# HexSwitch.net
KiCad netlist of a schematic drawn in Altium Designer
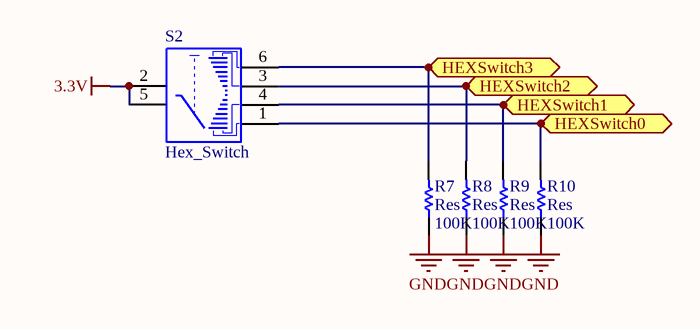
[diagram p0: HexSwitch.SchDoc]

(export (version "E")
  (design (tool "Eeschema 10.0.6"))
  (components
    (comp (ref "R7")
      (value "Res")
      (footprint "2012[0805]")
      (description "Semiconductor Resistor")
      (fields (field (name "ALTIUM_VALUE") "100K") (field (name "PUBLISHER") "Altium Limited"))
      (libsource (lib "KN2CLib") (part "Res"))
    )
    (comp (ref "R8")
      (value "Res")
      (footprint "2012[0805]")
      (description "Semiconductor Resistor")
      (fields (field (name "ALTIUM_VALUE") "100K") (field (name "PUBLISHER") "Altium Limited"))
      (libsource (lib "KN2CLib") (part "Res"))
    )
    (comp (ref "R9")
      (value "Res")
      (footprint "2012[0805]")
      (description "Semiconductor Resistor")
      (fields (field (name "ALTIUM_VALUE") "100K") (field (name "PUBLISHER") "Altium Limited"))
      (libsource (lib "KN2CLib") (part "Res"))
    )
    (comp (ref "R10")
      (value "Res")
      (footprint "2012[0805]")
      (description "Semiconductor Resistor")
      (fields (field (name "ALTIUM_VALUE") "100K") (field (name "PUBLISHER") "Altium Limited"))
      (libsource (lib "KN2CLib") (part "Res"))
    )
    (comp (ref "S2")
      (value "Hex_Switch")
      (footprint "SW-HEX")
      (description "SW-Hex")
      (fields (field (name "PUBLISHER") "Altium Limited"))
      (libsource (lib "KN2CLib") (part "SW-Hex"))
    )
  )
  (nets
    (net (code "1") (name "/HEXSwitch0") (class "Default")
      (node (ref "R10") (pin "2") (pinfunction "2_2") (pintype "passive"))
      (node (ref "S2") (pin "1") (pinfunction "1_1") (pintype "passive"))
    )
    (net (code "2") (name "/HEXSwitch1") (class "Default")
      (node (ref "R9") (pin "2") (pinfunction "2_2") (pintype "passive"))
      (node (ref "S2") (pin "4") (pinfunction "4_4") (pintype "passive"))
    )
    (net (code "3") (name "/HEXSwitch2") (class "Default")
      (node (ref "R8") (pin "2") (pinfunction "2_2") (pintype "passive"))
      (node (ref "S2") (pin "3") (pinfunction "3_3") (pintype "passive"))
    )
    (net (code "4") (name "/HEXSwitch3") (class "Default")
      (node (ref "R7") (pin "2") (pinfunction "2_2") (pintype "passive"))
      (node (ref "S2") (pin "6") (pinfunction "6_6") (pintype "passive"))
    )
    (net (code "5") (name "3.3V") (class "Default")
      (node (ref "S2") (pin "2") (pinfunction "2_2") (pintype "passive"))
      (node (ref "S2") (pin "5") (pinfunction "5_5") (pintype "passive"))
    )
    (net (code "6") (name "GND") (class "Default")
      (node (ref "R10") (pin "1") (pinfunction "1_1") (pintype "passive"))
      (node (ref "R7") (pin "1") (pinfunction "1_1") (pintype "passive"))
      (node (ref "R8") (pin "1") (pinfunction "1_1") (pintype "passive"))
      (node (ref "R9") (pin "1") (pinfunction "1_1") (pintype "passive"))
    )
  )
)
